# FT232RL.net
KiCad netlist of a schematic drawn in EAGLE
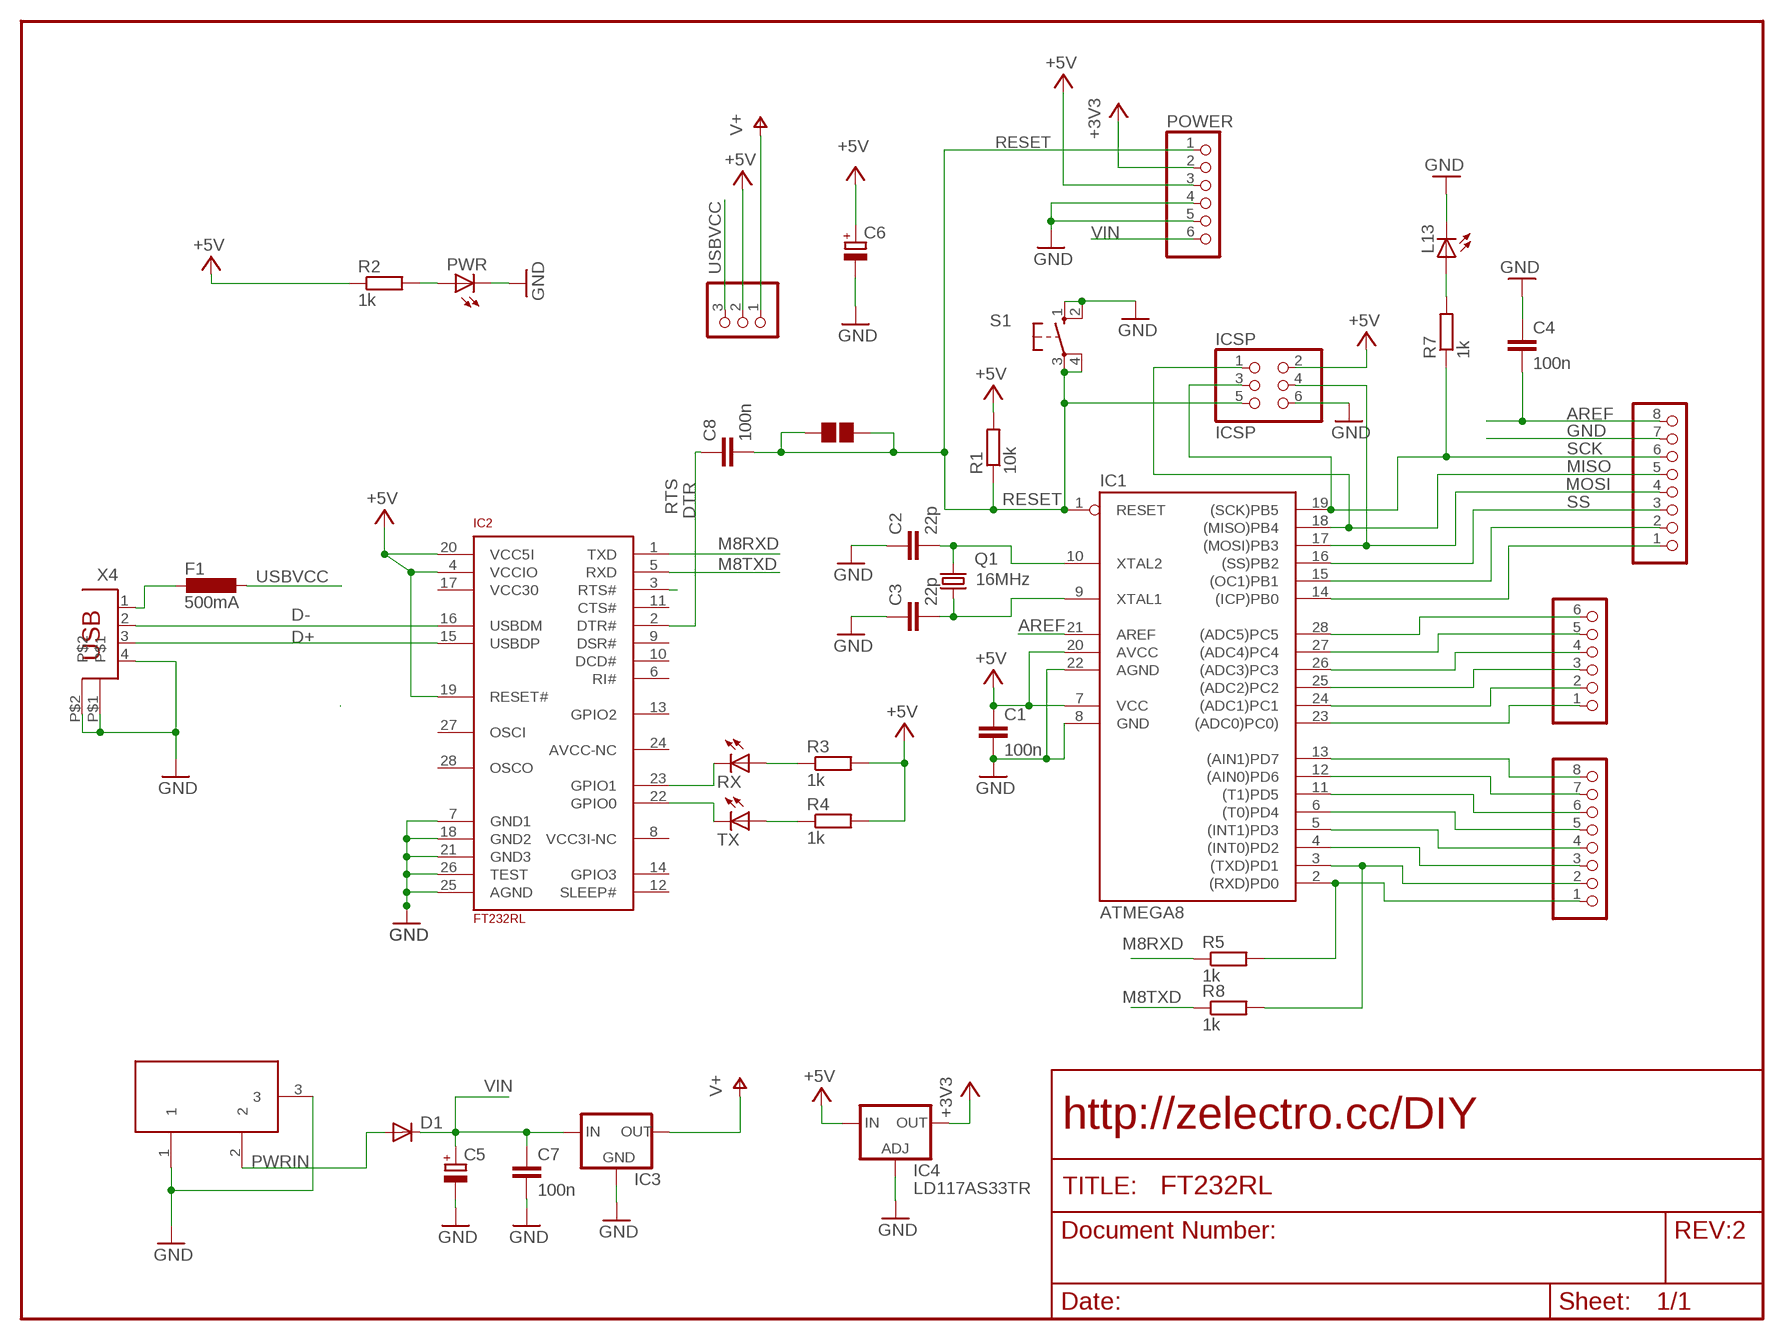
[diagram p0: schematic, sheet 1]

(export (version "E")
  (design (tool "Eeschema 10.0.6"))
  (components
    (comp (ref "C1")
      (value "100n")
      (footprint "eagle-import:C1206K")
      (libsource (lib "eagle-import") (part "C-EUC1206K"))
    )
    (comp (ref "C2")
      (value "22p")
      (footprint "eagle-import:C1206K")
      (libsource (lib "eagle-import") (part "C-EUC1206K"))
    )
    (comp (ref "C3")
      (value "22p")
      (footprint "eagle-import:C1206K")
      (libsource (lib "eagle-import") (part "C-EUC1206K"))
    )
    (comp (ref "C4")
      (value "100n")
      (footprint "eagle-import:C1206K")
      (libsource (lib "eagle-import") (part "C-EUC1206K"))
    )
    (comp (ref "C5")
      (value "CPOL-EUE2.5-7")
      (footprint "eagle-import:E2,5-7")
      (libsource (lib "eagle-import") (part "CPOL-EUE2.5-7"))
    )
    (comp (ref "C6")
      (value "CPOL-EUE2.5-7")
      (footprint "eagle-import:E2,5-7")
      (libsource (lib "eagle-import") (part "CPOL-EUE2.5-7"))
    )
    (comp (ref "C7")
      (value "100n")
      (footprint "eagle-import:C1206K")
      (libsource (lib "eagle-import") (part "C-EUC1206K"))
    )
    (comp (ref "C8")
      (value "100n")
      (footprint "eagle-import:C1206K")
      (libsource (lib "eagle-import") (part "C-EUC1206K"))
    )
    (comp (ref "D1")
      (value "DIODE-SMB")
      (footprint "eagle-import:SMB")
      (libsource (lib "eagle-import") (part "DIODE-SMB"))
    )
    (comp (ref "F1")
      (value "500mA")
      (footprint "eagle-import:L1812")
      (libsource (lib "eagle-import") (part "L-EUL1812"))
    )
    (comp (ref "IC1")
      (value "ATMEGA8")
      (footprint "eagle-import:DIL28-3")
      (libsource (lib "eagle-import") (part "AT90S4433P"))
    )
    (comp (ref "IC2")
      (value "FT232RL")
      (footprint "eagle-import:SSOP28")
      (libsource (lib "eagle-import") (part "FT232RL"))
    )
    (comp (ref "IC3")
      (value "78XXL")
      (footprint "eagle-import:78XXL")
      (libsource (lib "eagle-import") (part "78XXL"))
    )
    (comp (ref "IC4")
      (value "LD117AS33TR")
      (footprint "eagle-import:SOT223")
      (libsource (lib "eagle-import") (part "LD117A?S33TR"))
    )
    (comp (ref "ICSP")
      (value "ICSP")
      (footprint "eagle-import:2X03")
      (libsource (lib "eagle-import") (part "PINHD-2X3"))
    )
    (comp (ref "J1")
      (value "PINHD-1X8")
      (footprint "eagle-import:1X08")
      (libsource (lib "eagle-import") (part "PINHD-1X8"))
    )
    (comp (ref "J2")
      (value "PINHD-1X6")
      (footprint "eagle-import:1X06")
      (libsource (lib "eagle-import") (part "PINHD-1X6"))
    )
    (comp (ref "J3")
      (value "PINHD-1X8")
      (footprint "eagle-import:1X08")
      (libsource (lib "eagle-import") (part "PINHD-1X8"))
    )
    (comp (ref "JP3")
      (value "PINHD-1X3")
      (footprint "eagle-import:1X03")
      (libsource (lib "eagle-import") (part "PINHD-1X3"))
    )
    (comp (ref "L13")
      (value "LED3MM")
      (footprint "eagle-import:LED3MM")
      (libsource (lib "eagle-import") (part "LED3MM"))
    )
    (comp (ref "POWER")
      (value "PINHD-1X6")
      (footprint "eagle-import:1X06")
      (libsource (lib "eagle-import") (part "PINHD-1X6"))
    )
    (comp (ref "PWR")
      (value "LED3MM")
      (footprint "eagle-import:LED3MM")
      (libsource (lib "eagle-import") (part "LED3MM"))
    )
    (comp (ref "Q1")
      (value "16MHz")
      (footprint "eagle-import:HC49_S")
      (libsource (lib "eagle-import") (part "CRYTALHC49S"))
    )
    (comp (ref "R1")
      (value "10k")
      (footprint "eagle-import:M1406")
      (libsource (lib "eagle-import") (part "R-EU_M1406"))
    )
    (comp (ref "R2")
      (value "1k")
      (footprint "eagle-import:M1406")
      (libsource (lib "eagle-import") (part "R-EU_M1406"))
    )
    (comp (ref "R3")
      (value "1k")
      (footprint "eagle-import:M1406")
      (libsource (lib "eagle-import") (part "R-EU_M1406"))
    )
    (comp (ref "R4")
      (value "1k")
      (footprint "eagle-import:M1406")
      (libsource (lib "eagle-import") (part "R-EU_M1406"))
    )
    (comp (ref "R5")
      (value "1k")
      (footprint "eagle-import:M1406")
      (libsource (lib "eagle-import") (part "R-EU_M1406"))
    )
    (comp (ref "R7")
      (value "1k")
      (footprint "eagle-import:M1406")
      (libsource (lib "eagle-import") (part "R-EU_M1406"))
    )
    (comp (ref "R8")
      (value "1k")
      (footprint "eagle-import:M1406")
      (libsource (lib "eagle-import") (part "R-EU_M1406"))
    )
    (comp (ref "RX")
      (value "LED3MM")
      (footprint "eagle-import:LED3MM")
      (libsource (lib "eagle-import") (part "LED3MM"))
    )
    (comp (ref "S1")
      (value "10-XX")
      (footprint "eagle-import:B3F-10XX")
      (libsource (lib "eagle-import") (part "10-XX"))
    )
    (comp (ref "TX")
      (value "LED3MM")
      (footprint "eagle-import:LED3MM")
      (libsource (lib "eagle-import") (part "LED3MM"))
    )
    (comp (ref "X2")
      (value "DC21MMX")
      (footprint "eagle-import:DC-21MM")
      (libsource (lib "eagle-import") (part "DC21MMX"))
    )
    (comp (ref "X4")
      (value "PN61729")
      (footprint "eagle-import:PN61729")
      (libsource (lib "eagle-import") (part "PN61729"))
    )
  )
  (nets
    (net (code "1") (name "+3V3") (class "Default")
      (node (ref "IC4") (pin "4") (pinfunction "OUT_4") (pintype "passive"))
      (node (ref "POWER") (pin "2") (pinfunction "2_2") (pintype "passive"))
    )
    (net (code "2") (name "+5V") (class "Default")
      (node (ref "C1") (pin "1") (pinfunction "1_1") (pintype "passive"))
      (node (ref "C6") (pin "+") (pinfunction "+_+") (pintype "passive"))
      (node (ref "IC1") (pin "20") (pinfunction "AVCC_20") (pintype "power_in"))
      (node (ref "IC1") (pin "7") (pinfunction "VCC_7") (pintype "power_in"))
      (node (ref "IC2") (pin "19") (pinfunction "RESET#_19") (pintype "input"))
      (node (ref "IC2") (pin "20") (pinfunction "VCC5I_20") (pintype "power_in"))
      (node (ref "IC2") (pin "4") (pinfunction "VCCIO_4") (pintype "power_in"))
      (node (ref "IC4") (pin "3") (pinfunction "IN_3") (pintype "input"))
      (node (ref "ICSP") (pin "2") (pinfunction "2_2") (pintype "passive"))
      (node (ref "JP3") (pin "2") (pinfunction "2_2") (pintype "passive"))
      (node (ref "POWER") (pin "3") (pinfunction "3_3") (pintype "passive"))
      (node (ref "R1") (pin "2") (pinfunction "2_2") (pintype "passive"))
      (node (ref "R2") (pin "1") (pinfunction "1_1") (pintype "passive"))
      (node (ref "R3") (pin "2") (pinfunction "2_2") (pintype "passive"))
      (node (ref "R4") (pin "2") (pinfunction "2_2") (pintype "passive"))
    )
    (net (code "3") (name "/AREF") (class "Default")
      (node (ref "C4") (pin "2") (pinfunction "2_2") (pintype "passive"))
      (node (ref "IC1") (pin "21") (pinfunction "AREF_21") (pintype "power_in"))
      (node (ref "J3") (pin "8") (pinfunction "8_8") (pintype "passive"))
    )
    (net (code "4") (name "/D+") (class "Default")
      (node (ref "IC2") (pin "15") (pinfunction "USBDP_15") (pintype "bidirectional"))
      (node (ref "X4") (pin "3") (pinfunction "3_3") (pintype "bidirectional"))
    )
    (net (code "5") (name "/D-") (class "Default")
      (node (ref "IC2") (pin "16") (pinfunction "USBDM_16") (pintype "bidirectional"))
      (node (ref "X4") (pin "2") (pinfunction "2_2") (pintype "bidirectional"))
    )
    (net (code "6") (name "/DTR") (class "Default")
      (node (ref "C8") (pin "1") (pinfunction "1_1") (pintype "passive"))
      (node (ref "IC2") (pin "2") (pinfunction "DTR#_2") (pintype "output"))
    )
    (net (code "7") (name "/M8RXD") (class "Default")
      (node (ref "IC2") (pin "1") (pinfunction "TXD_1") (pintype "output"))
      (node (ref "R5") (pin "1") (pinfunction "1_1") (pintype "passive"))
    )
    (net (code "8") (name "/M8TXD") (class "Default")
      (node (ref "IC2") (pin "5") (pinfunction "RXD_5") (pintype "input"))
      (node (ref "R8") (pin "1") (pinfunction "1_1") (pintype "passive"))
    )
    (net (code "9") (name "/MISO") (class "Default")
      (node (ref "IC1") (pin "18") (pinfunction "(MISO)PB4_18") (pintype "bidirectional"))
      (node (ref "ICSP") (pin "1") (pinfunction "1_1") (pintype "passive"))
      (node (ref "J3") (pin "5") (pinfunction "5_5") (pintype "passive"))
    )
    (net (code "10") (name "/MOSI") (class "Default")
      (node (ref "IC1") (pin "17") (pinfunction "(MOSI)PB3_17") (pintype "bidirectional"))
      (node (ref "ICSP") (pin "4") (pinfunction "4_4") (pintype "passive"))
      (node (ref "J3") (pin "4") (pinfunction "4_4") (pintype "passive"))
    )
    (net (code "11") (name "/PWRIN") (class "Default")
      (node (ref "D1") (pin "A") (pinfunction "A_A") (pintype "passive"))
      (node (ref "X2") (pin "2") (pinfunction "2_2") (pintype "power_in"))
    )
    (net (code "12") (name "/RESET") (class "Default")
      (node (ref "C8") (pin "2") (pinfunction "2_2") (pintype "passive"))
      (node (ref "IC1") (pin "1") (pinfunction "RESET_1") (pintype "input"))
      (node (ref "ICSP") (pin "5") (pinfunction "5_5") (pintype "passive"))
      (node (ref "POWER") (pin "1") (pinfunction "1_1") (pintype "passive"))
      (node (ref "R1") (pin "1") (pinfunction "1_1") (pintype "passive"))
      (node (ref "S1") (pin "3") (pinfunction "P_3") (pintype "passive"))
      (node (ref "S1") (pin "4") (pinfunction "P1_4") (pintype "passive"))
    )
    (net (code "13") (name "/RTS") (class "Default")
      (node (ref "IC2") (pin "3") (pinfunction "RTS#_3") (pintype "output"))
    )
    (net (code "14") (name "/SCK") (class "Default")
      (node (ref "IC1") (pin "19") (pinfunction "(SCK)PB5_19") (pintype "bidirectional"))
      (node (ref "ICSP") (pin "3") (pinfunction "3_3") (pintype "passive"))
      (node (ref "J3") (pin "6") (pinfunction "6_6") (pintype "passive"))
      (node (ref "R7") (pin "1") (pinfunction "1_1") (pintype "passive"))
    )
    (net (code "15") (name "/SS") (class "Default")
      (node (ref "IC1") (pin "16") (pinfunction "(SS)PB2_16") (pintype "bidirectional"))
      (node (ref "J3") (pin "3") (pinfunction "3_3") (pintype "passive"))
    )
    (net (code "16") (name "/USBVCC") (class "Default")
      (node (ref "F1") (pin "1") (pinfunction "1_1") (pintype "passive"))
      (node (ref "JP3") (pin "3") (pinfunction "3_3") (pintype "passive"))
    )
    (net (code "17") (name "/VCC30") (class "Default")
      (node (ref "IC2") (pin "17") (pinfunction "VCC30_17") (pintype "power_in"))
    )
    (net (code "18") (name "/VIN") (class "Default")
      (node (ref "C5") (pin "+") (pinfunction "+_+") (pintype "passive"))
      (node (ref "C7") (pin "1") (pinfunction "1_1") (pintype "passive"))
      (node (ref "D1") (pin "C") (pinfunction "C_C") (pintype "passive"))
      (node (ref "IC3") (pin "IN") (pinfunction "IN_IN") (pintype "input"))
      (node (ref "POWER") (pin "6") (pinfunction "6_6") (pintype "passive"))
    )
    (net (code "19") (name "GND") (class "Default")
      (node (ref "C1") (pin "2") (pinfunction "2_2") (pintype "passive"))
      (node (ref "C2") (pin "1") (pinfunction "1_1") (pintype "passive"))
      (node (ref "C3") (pin "1") (pinfunction "1_1") (pintype "passive"))
      (node (ref "C4") (pin "1") (pinfunction "1_1") (pintype "passive"))
      (node (ref "C5") (pin "-") (pinfunction "-_-") (pintype "passive"))
      (node (ref "C6") (pin "-") (pinfunction "-_-") (pintype "passive"))
      (node (ref "C7") (pin "2") (pinfunction "2_2") (pintype "passive"))
      (node (ref "IC1") (pin "22") (pinfunction "AGND_22") (pintype "power_in"))
      (node (ref "IC1") (pin "8") (pinfunction "GND_8") (pintype "power_in"))
      (node (ref "IC2") (pin "18") (pinfunction "GND2_18") (pintype "power_in"))
      (node (ref "IC2") (pin "21") (pinfunction "GND3_21") (pintype "power_in"))
      (node (ref "IC2") (pin "25") (pinfunction "AGND_25") (pintype "power_in"))
      (node (ref "IC2") (pin "26") (pinfunction "TEST_26") (pintype "input"))
      (node (ref "IC2") (pin "7") (pinfunction "GND1_7") (pintype "power_in"))
      (node (ref "IC3") (pin "GND") (pinfunction "GND_GND") (pintype "input"))
      (node (ref "IC4") (pin "1") (pinfunction "ADJ_1") (pintype "input"))
      (node (ref "ICSP") (pin "6") (pinfunction "6_6") (pintype "passive"))
      (node (ref "J3") (pin "7") (pinfunction "7_7") (pintype "passive"))
      (node (ref "L13") (pin "K") (pinfunction "C_K") (pintype "passive"))
      (node (ref "POWER") (pin "4") (pinfunction "4_4") (pintype "passive"))
      (node (ref "POWER") (pin "5") (pinfunction "5_5") (pintype "passive"))
      (node (ref "PWR") (pin "K") (pinfunction "C_K") (pintype "passive"))
      (node (ref "S1") (pin "1") (pinfunction "S_1") (pintype "passive"))
      (node (ref "S1") (pin "2") (pinfunction "S1_2") (pintype "passive"))
      (node (ref "X2") (pin "1") (pinfunction "1_1") (pintype "power_in"))
      (node (ref "X2") (pin "3") (pinfunction "3_3") (pintype "power_in"))
      (node (ref "X4") (pin "4") (pinfunction "4_4") (pintype "bidirectional"))
      (node (ref "X4") (pin "P$1") (pinfunction "P$1_P$1") (pintype "bidirectional"))
      (node (ref "X4") (pin "P$2") (pinfunction "P$2_P$2") (pintype "bidirectional"))
    )
    (net (code "20") (name "Net-(F1-Pad2)") (class "Default")
      (node (ref "F1") (pin "2") (pinfunction "2_2") (pintype "passive"))
      (node (ref "X4") (pin "1") (pinfunction "1_1") (pintype "bidirectional"))
    )
    (net (code "21") (name "Net-(IC1-(ADC0)PC0))") (class "Default")
      (node (ref "IC1") (pin "23") (pinfunction "(ADC0)PC0)_23") (pintype "bidirectional"))
      (node (ref "J2") (pin "1") (pinfunction "1_1") (pintype "passive"))
    )
    (net (code "22") (name "Net-(IC1-(ADC1)PC1)") (class "Default")
      (node (ref "IC1") (pin "24") (pinfunction "(ADC1)PC1_24") (pintype "bidirectional"))
      (node (ref "J2") (pin "2") (pinfunction "2_2") (pintype "passive"))
    )
    (net (code "23") (name "Net-(IC1-(ADC2)PC2)") (class "Default")
      (node (ref "IC1") (pin "25") (pinfunction "(ADC2)PC2_25") (pintype "bidirectional"))
      (node (ref "J2") (pin "3") (pinfunction "3_3") (pintype "passive"))
    )
    (net (code "24") (name "Net-(IC1-(ADC3)PC3)") (class "Default")
      (node (ref "IC1") (pin "26") (pinfunction "(ADC3)PC3_26") (pintype "bidirectional"))
      (node (ref "J2") (pin "4") (pinfunction "4_4") (pintype "passive"))
    )
    (net (code "25") (name "Net-(IC1-(ADC4)PC4)") (class "Default")
      (node (ref "IC1") (pin "27") (pinfunction "(ADC4)PC4_27") (pintype "bidirectional"))
      (node (ref "J2") (pin "5") (pinfunction "5_5") (pintype "passive"))
    )
    (net (code "26") (name "Net-(IC1-(ADC5)PC5)") (class "Default")
      (node (ref "IC1") (pin "28") (pinfunction "(ADC5)PC5_28") (pintype "bidirectional"))
      (node (ref "J2") (pin "6") (pinfunction "6_6") (pintype "passive"))
    )
    (net (code "27") (name "Net-(IC1-(AIN0)PD6)") (class "Default")
      (node (ref "IC1") (pin "12") (pinfunction "(AIN0)PD6_12") (pintype "bidirectional"))
      (node (ref "J1") (pin "7") (pinfunction "7_7") (pintype "passive"))
    )
    (net (code "28") (name "Net-(IC1-(AIN1)PD7)") (class "Default")
      (node (ref "IC1") (pin "13") (pinfunction "(AIN1)PD7_13") (pintype "bidirectional"))
      (node (ref "J1") (pin "8") (pinfunction "8_8") (pintype "passive"))
    )
    (net (code "29") (name "Net-(IC1-(ICP)PB0)") (class "Default")
      (node (ref "IC1") (pin "14") (pinfunction "(ICP)PB0_14") (pintype "bidirectional"))
      (node (ref "J3") (pin "1") (pinfunction "1_1") (pintype "passive"))
    )
    (net (code "30") (name "Net-(IC1-(INT0)PD2)") (class "Default")
      (node (ref "IC1") (pin "4") (pinfunction "(INT0)PD2_4") (pintype "bidirectional"))
      (node (ref "J1") (pin "3") (pinfunction "3_3") (pintype "passive"))
    )
    (net (code "31") (name "Net-(IC1-(INT1)PD3)") (class "Default")
      (node (ref "IC1") (pin "5") (pinfunction "(INT1)PD3_5") (pintype "bidirectional"))
      (node (ref "J1") (pin "4") (pinfunction "4_4") (pintype "passive"))
    )
    (net (code "32") (name "Net-(IC1-(OC1)PB1)") (class "Default")
      (node (ref "IC1") (pin "15") (pinfunction "(OC1)PB1_15") (pintype "bidirectional"))
      (node (ref "J3") (pin "2") (pinfunction "2_2") (pintype "passive"))
    )
    (net (code "33") (name "Net-(IC1-(RXD)PD0)") (class "Default")
      (node (ref "IC1") (pin "2") (pinfunction "(RXD)PD0_2") (pintype "bidirectional"))
      (node (ref "J1") (pin "1") (pinfunction "1_1") (pintype "passive"))
      (node (ref "R5") (pin "2") (pinfunction "2_2") (pintype "passive"))
    )
    (net (code "34") (name "Net-(IC1-(T0)PD4)") (class "Default")
      (node (ref "IC1") (pin "6") (pinfunction "(T0)PD4_6") (pintype "bidirectional"))
      (node (ref "J1") (pin "5") (pinfunction "5_5") (pintype "passive"))
    )
    (net (code "35") (name "Net-(IC1-(T1)PD5)") (class "Default")
      (node (ref "IC1") (pin "11") (pinfunction "(T1)PD5_11") (pintype "bidirectional"))
      (node (ref "J1") (pin "6") (pinfunction "6_6") (pintype "passive"))
    )
    (net (code "36") (name "Net-(IC1-(TXD)PD1)") (class "Default")
      (node (ref "IC1") (pin "3") (pinfunction "(TXD)PD1_3") (pintype "bidirectional"))
      (node (ref "J1") (pin "2") (pinfunction "2_2") (pintype "passive"))
      (node (ref "R8") (pin "2") (pinfunction "2_2") (pintype "passive"))
    )
    (net (code "37") (name "Net-(IC1-XTAL1)") (class "Default")
      (node (ref "C3") (pin "2") (pinfunction "2_2") (pintype "passive"))
      (node (ref "IC1") (pin "9") (pinfunction "XTAL1_9") (pintype "bidirectional"))
      (node (ref "Q1") (pin "1") (pinfunction "1_1") (pintype "passive"))
    )
    (net (code "38") (name "Net-(IC1-XTAL2)") (class "Default")
      (node (ref "C2") (pin "2") (pinfunction "2_2") (pintype "passive"))
      (node (ref "IC1") (pin "10") (pinfunction "XTAL2_10") (pintype "bidirectional"))
      (node (ref "Q1") (pin "2") (pinfunction "2_2") (pintype "passive"))
    )
    (net (code "39") (name "Net-(IC2-GPIO0)") (class "Default")
      (node (ref "IC2") (pin "22") (pinfunction "GPIO0_22") (pintype "output"))
      (node (ref "TX") (pin "K") (pinfunction "C_K") (pintype "passive"))
    )
    (net (code "40") (name "Net-(IC2-GPIO1)") (class "Default")
      (node (ref "IC2") (pin "23") (pinfunction "GPIO1_23") (pintype "output"))
      (node (ref "RX") (pin "K") (pinfunction "C_K") (pintype "passive"))
    )
    (net (code "41") (name "Net-(L13-PadA)") (class "Default")
      (node (ref "L13") (pin "A") (pinfunction "A_A") (pintype "passive"))
      (node (ref "R7") (pin "2") (pinfunction "2_2") (pintype "passive"))
    )
    (net (code "42") (name "Net-(PWR-PadA)") (class "Default")
      (node (ref "PWR") (pin "A") (pinfunction "A_A") (pintype "passive"))
      (node (ref "R2") (pin "2") (pinfunction "2_2") (pintype "passive"))
    )
    (net (code "43") (name "Net-(R3-Pad1)") (class "Default")
      (node (ref "R3") (pin "1") (pinfunction "1_1") (pintype "passive"))
      (node (ref "RX") (pin "A") (pinfunction "A_A") (pintype "passive"))
    )
    (net (code "44") (name "Net-(R4-Pad1)") (class "Default")
      (node (ref "R4") (pin "1") (pinfunction "1_1") (pintype "passive"))
      (node (ref "TX") (pin "A") (pinfunction "A_A") (pintype "passive"))
    )
    (net (code "45") (name "V+") (class "Default")
      (node (ref "IC3") (pin "OUT") (pinfunction "OUT_OUT") (pintype "passive"))
      (node (ref "JP3") (pin "1") (pinfunction "1_1") (pintype "passive"))
    )
    (net (code "46") (name "unconnected-(IC2-AVCC-NC-Pad24)") (class "Default")
      (node (ref "IC2") (pin "24") (pinfunction "AVCC-NC_24") (pintype "no_connect"))
    )
    (net (code "47") (name "unconnected-(IC2-CTS#-Pad11)") (class "Default")
      (node (ref "IC2") (pin "11") (pinfunction "CTS#_11") (pintype "input"))
    )
    (net (code "48") (name "unconnected-(IC2-DCD#-Pad10)") (class "Default")
      (node (ref "IC2") (pin "10") (pinfunction "DCD#_10") (pintype "input"))
    )
    (net (code "49") (name "unconnected-(IC2-DSR#-Pad9)") (class "Default")
      (node (ref "IC2") (pin "9") (pinfunction "DSR#_9") (pintype "input"))
    )
    (net (code "50") (name "unconnected-(IC2-GPIO2-Pad13)") (class "Default")
      (node (ref "IC2") (pin "13") (pinfunction "GPIO2_13") (pintype "output"))
    )
    (net (code "51") (name "unconnected-(IC2-GPIO3-Pad14)") (class "Default")
      (node (ref "IC2") (pin "14") (pinfunction "GPIO3_14") (pintype "input"))
    )
    (net (code "52") (name "unconnected-(IC2-OSCI-Pad27)") (class "Default")
      (node (ref "IC2") (pin "27") (pinfunction "OSCI_27") (pintype "input"))
    )
    (net (code "53") (name "unconnected-(IC2-OSCO-Pad28)") (class "Default")
      (node (ref "IC2") (pin "28") (pinfunction "OSCO_28") (pintype "output"))
    )
    (net (code "54") (name "unconnected-(IC2-RI#-Pad6)") (class "Default")
      (node (ref "IC2") (pin "6") (pinfunction "RI#_6") (pintype "input"))
    )
    (net (code "55") (name "unconnected-(IC2-SLEEP#-Pad12)") (class "Default")
      (node (ref "IC2") (pin "12") (pinfunction "SLEEP#_12") (pintype "input"))
    )
    (net (code "56") (name "unconnected-(IC2-VCC3I-NC-Pad8)") (class "Default")
      (node (ref "IC2") (pin "8") (pinfunction "VCC3I-NC_8") (pintype "no_connect"))
    )
  )
)
